# GYRO_3-AXIS_-_ITG-3200.net
KiCad netlist of a schematic drawn in Altium Designer
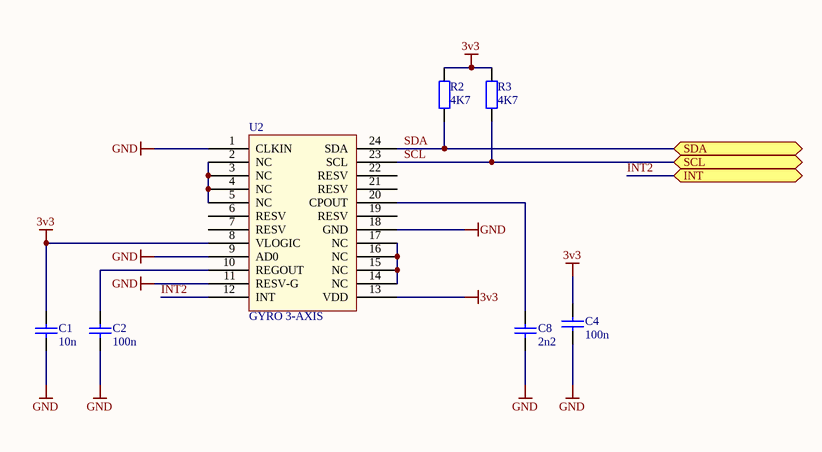
[diagram p0: GYRO 3-AXIS - ITG-3200.SchDoc]

(export (version "E")
  (design (tool "Eeschema 10.0.6"))
  (components
    (comp (ref "C1")
      (value "10n")
      (footprint "C0805")
      (fields (field (name "TOLERANCE") "0.1") (field (name "AUTHOR") "Willy Pietersz"))
      (libsource (lib "OurDb") (part "cap_NonPolar"))
    )
    (comp (ref "C2")
      (value "100n")
      (footprint "C0805")
      (fields (field (name "TOLERANCE") "0.1") (field (name "AUTHOR") "Willy Pietersz"))
      (libsource (lib "OurDb") (part "cap_NonPolar"))
    )
    (comp (ref "C4")
      (value "100n")
      (footprint "C0805")
      (fields (field (name "TOLERANCE") "0.1") (field (name "AUTHOR") "Willy Pietersz"))
      (libsource (lib "OurDb") (part "cap_NonPolar"))
    )
    (comp (ref "C8")
      (value "2n2")
      (footprint "C0805")
      (fields (field (name "TOLERANCE") "0.1") (field (name "AUTHOR") "Willy Pietersz"))
      (libsource (lib "OurDb") (part "cap_NonPolar"))
    )
    (comp (ref "R2")
      (value "4K7")
      (footprint "R0805")
      (description "Resistor")
      (fields
        (field (name "POWER") "0.25W")
        (field (name "TOLERANCE") "0.05")
        (field (name "PUBLISHER") "Altium Limited")
        (field (name "AUTHOR") "Willy Pietersz")
      )
      (libsource (lib "OurDb") (part "RESISTOR"))
    )
    (comp (ref "R3")
      (value "4K7")
      (footprint "R0805")
      (description "Resistor")
      (fields
        (field (name "POWER") "0.25W")
        (field (name "TOLERANCE") "0.05")
        (field (name "PUBLISHER") "Altium Limited")
        (field (name "AUTHOR") "Willy Pietersz")
      )
      (libsource (lib "OurDb") (part "RESISTOR"))
    )
    (comp (ref "U2")
      (value "GYRO 3-AXIS")
      (footprint "QFN50P400X400-24V2M - GYRO 3axis")
      (description "Gyro, 3-axis")
      (fields (field (name "PART NUMBER") "ITG-3200"))
      (libsource (lib "OurDb") (part "ITG-3200"))
    )
  )
  (nets
    (net (code "1") (name "/INT2") (class "Default")
      (node (ref "U2") (pin "12") (pinfunction "INT_12") (pintype "passive"))
    )
    (net (code "2") (name "/SCL") (class "Default")
      (node (ref "R3") (pin "2") (pinfunction "2_2") (pintype "passive"))
      (node (ref "U2") (pin "23") (pinfunction "SCL_23") (pintype "passive"))
    )
    (net (code "3") (name "/SDA") (class "Default")
      (node (ref "R2") (pin "2") (pinfunction "2_2") (pintype "passive"))
      (node (ref "U2") (pin "24") (pinfunction "SDA_24") (pintype "passive"))
    )
    (net (code "4") (name "3v3") (class "Default")
      (node (ref "C1") (pin "2") (pinfunction "2_2") (pintype "passive"))
      (node (ref "C4") (pin "2") (pinfunction "2_2") (pintype "passive"))
      (node (ref "R2") (pin "1") (pinfunction "1_1") (pintype "passive"))
      (node (ref "R3") (pin "1") (pinfunction "1_1") (pintype "passive"))
      (node (ref "U2") (pin "13") (pinfunction "VDD_13") (pintype "passive"))
      (node (ref "U2") (pin "8") (pinfunction "VLOGIC_8") (pintype "passive"))
    )
    (net (code "5") (name "GND") (class "Default")
      (node (ref "C1") (pin "1") (pinfunction "1_1") (pintype "passive"))
      (node (ref "C2") (pin "1") (pinfunction "1_1") (pintype "passive"))
      (node (ref "C4") (pin "1") (pinfunction "1_1") (pintype "passive"))
      (node (ref "C8") (pin "1") (pinfunction "1_1") (pintype "passive"))
      (node (ref "U2") (pin "1") (pinfunction "CLKIN_1") (pintype "passive"))
      (node (ref "U2") (pin "11") (pinfunction "RESV-G_11") (pintype "passive"))
      (node (ref "U2") (pin "18") (pinfunction "GND_18") (pintype "passive"))
      (node (ref "U2") (pin "9") (pinfunction "AD0_9") (pintype "passive"))
    )
    (net (code "6") (name "Net-(U2-CPOUT)") (class "Default")
      (node (ref "C8") (pin "2") (pinfunction "2_2") (pintype "passive"))
      (node (ref "U2") (pin "20") (pinfunction "CPOUT_20") (pintype "passive"))
    )
    (net (code "7") (name "Net-(U2-NC-Pad2)") (class "Default")
      (node (ref "U2") (pin "2") (pinfunction "NC_2") (pintype "passive"))
      (node (ref "U2") (pin "3") (pinfunction "NC_3") (pintype "passive"))
      (node (ref "U2") (pin "4") (pinfunction "NC_4") (pintype "passive"))
      (node (ref "U2") (pin "5") (pinfunction "NC_5") (pintype "passive"))
    )
    (net (code "8") (name "Net-(U2-NC-Pad14)") (class "Default")
      (node (ref "U2") (pin "14") (pinfunction "NC_14") (pintype "passive"))
      (node (ref "U2") (pin "15") (pinfunction "NC_15") (pintype "passive"))
      (node (ref "U2") (pin "16") (pinfunction "NC_16") (pintype "passive"))
      (node (ref "U2") (pin "17") (pinfunction "NC_17") (pintype "passive"))
    )
    (net (code "9") (name "Net-(U2-REGOUT)") (class "Default")
      (node (ref "C2") (pin "2") (pinfunction "2_2") (pintype "passive"))
      (node (ref "U2") (pin "10") (pinfunction "REGOUT_10") (pintype "passive"))
    )
    (net (code "10") (name "unconnected-(U2-RESV-Pad6)") (class "Default")
      (node (ref "U2") (pin "6") (pinfunction "RESV_6") (pintype "passive"))
    )
    (net (code "11") (name "unconnected-(U2-RESV-Pad7)") (class "Default")
      (node (ref "U2") (pin "7") (pinfunction "RESV_7") (pintype "passive"))
    )
    (net (code "12") (name "unconnected-(U2-RESV-Pad19)") (class "Default")
      (node (ref "U2") (pin "19") (pinfunction "RESV_19") (pintype "passive"))
    )
    (net (code "13") (name "unconnected-(U2-RESV-Pad21)") (class "Default")
      (node (ref "U2") (pin "21") (pinfunction "RESV_21") (pintype "passive"))
    )
    (net (code "14") (name "unconnected-(U2-RESV-Pad22)") (class "Default")
      (node (ref "U2") (pin "22") (pinfunction "RESV_22") (pintype "passive"))
    )
  )
)
